# PIR_Relay.net
KiCad netlist of a schematic drawn in EAGLE
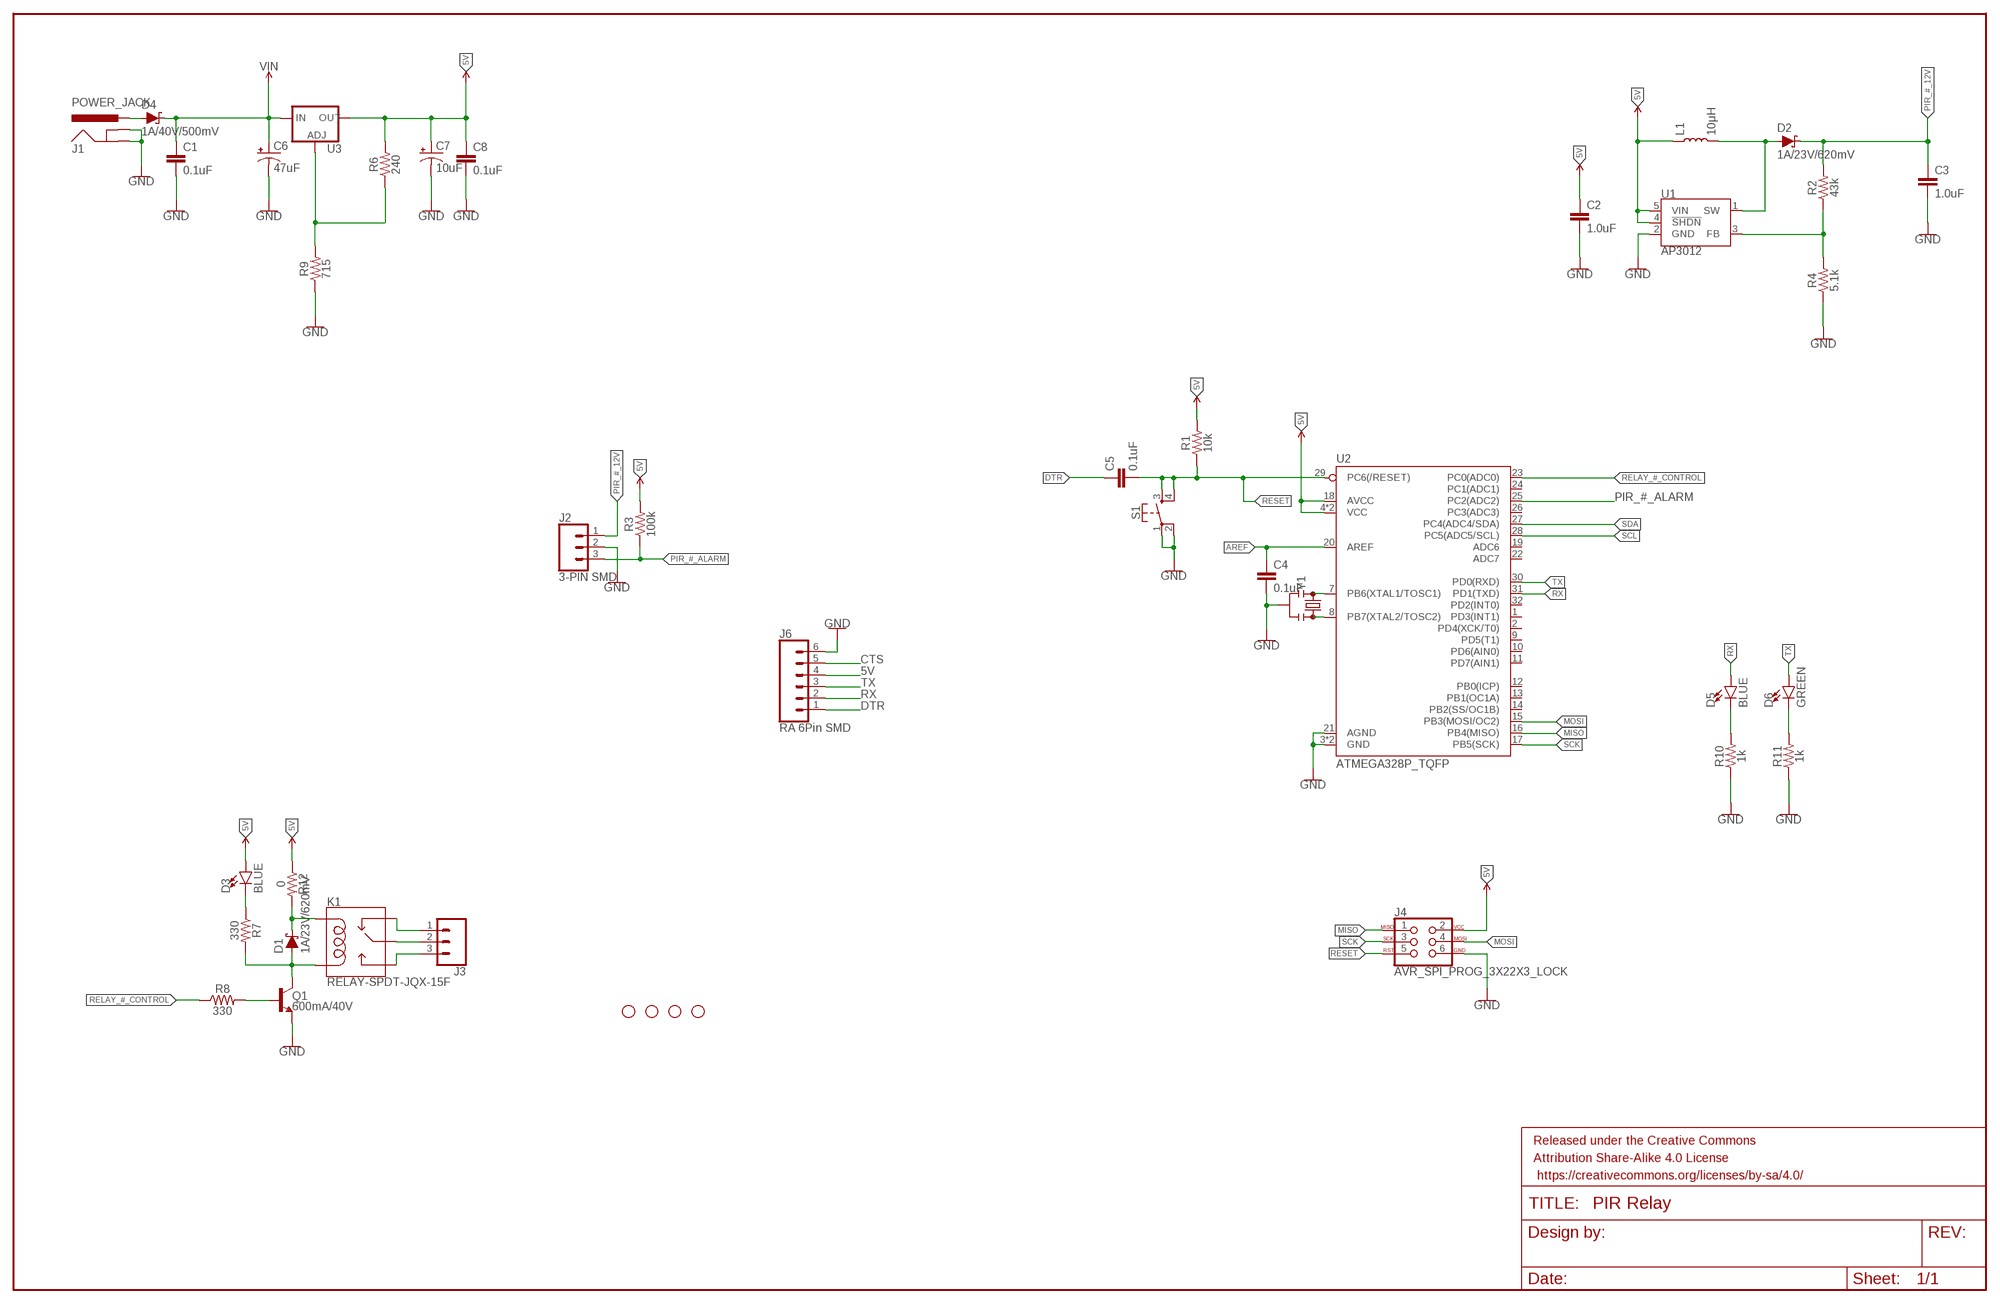
[diagram p0: schematic, sheet 1]

(export (version "E")
  (design (tool "Eeschema 10.0.6"))
  (components
    (comp (ref "C1")
      (value "0.1uF")
      (footprint "eagle-import:0603")
      (libsource (lib "eagle-import") (part "SparkFun-Capacitors_510_0.1UF-0603-25V-5%"))
    )
    (comp (ref "C2")
      (value "1.0uF")
      (footprint "eagle-import:0603")
      (libsource (lib "eagle-import") (part "1.0UF-0603-16V-10%"))
    )
    (comp (ref "C3")
      (value "1.0uF")
      (footprint "eagle-import:0603")
      (libsource (lib "eagle-import") (part "1.0UF-0603-16V-10%"))
    )
    (comp (ref "C4")
      (value "0.1uF")
      (footprint "eagle-import:0603")
      (libsource (lib "eagle-import") (part "0.1UF-0603-25V-(+80/-20%)"))
    )
    (comp (ref "C5")
      (value "0.1uF")
      (footprint "eagle-import:0603")
      (libsource (lib "eagle-import") (part "0.1UF-0603-25V-(+80/-20%)"))
    )
    (comp (ref "C6")
      (value "47uF")
      (footprint "eagle-import:PANASONIC_D")
      (libsource (lib "eagle-import") (part "47UF-POLAR-PANASONIC_D-35V-20%"))
    )
    (comp (ref "C7")
      (value "10uF")
      (footprint "eagle-import:EIA3216")
      (libsource (lib "eagle-import") (part "10UF-POLAR-EIA3216-16V-10%(TANT)"))
    )
    (comp (ref "C8")
      (value "0.1uF")
      (footprint "eagle-import:0603")
      (libsource (lib "eagle-import") (part "0.1UF-0603-25V-(+80/-20%)"))
    )
    (comp (ref "D1")
      (value "1A/23V/620mV")
      (footprint "eagle-import:SOD-323")
      (libsource (lib "eagle-import") (part "DIODE-SCHOTTKY-BAT20J"))
    )
    (comp (ref "D2")
      (value "1A/23V/620mV")
      (footprint "eagle-import:SOD-323")
      (libsource (lib "eagle-import") (part "DIODE-SCHOTTKY-BAT20J"))
    )
    (comp (ref "D3")
      (value "BLUE")
      (footprint "eagle-import:LED-0603")
      (libsource (lib "eagle-import") (part "LED-BLUE0603"))
    )
    (comp (ref "D4")
      (value "1A/40V/500mV")
      (footprint "eagle-import:SMA-DIODE")
      (libsource (lib "eagle-import") (part "DIODE-SCHOTTKY-SS14"))
    )
    (comp (ref "D5")
      (value "BLUE")
      (footprint "eagle-import:LED-0603")
      (libsource (lib "eagle-import") (part "LED-BLUE0603"))
    )
    (comp (ref "D6")
      (value "GREEN")
      (footprint "eagle-import:LED-0603")
      (libsource (lib "eagle-import") (part "LED-GREEN0603"))
    )
    (comp (ref "FRAME1")
      (value "FRAME-LEDGER")
      (footprint "eagle-import:CREATIVE_COMMONS")
      (libsource (lib "eagle-import") (part "FRAME-LEDGER"))
    )
    (comp (ref "H1")
      (value "STAND-OFF")
      (footprint "eagle-import:STAND-OFF")
      (libsource (lib "eagle-import") (part "STAND-OFF"))
    )
    (comp (ref "H2")
      (value "STAND-OFF")
      (footprint "eagle-import:STAND-OFF")
      (libsource (lib "eagle-import") (part "STAND-OFF"))
    )
    (comp (ref "H3")
      (value "STAND-OFF")
      (footprint "eagle-import:STAND-OFF")
      (libsource (lib "eagle-import") (part "STAND-OFF"))
    )
    (comp (ref "H4")
      (value "STAND-OFF")
      (footprint "eagle-import:STAND-OFF")
      (libsource (lib "eagle-import") (part "STAND-OFF"))
    )
    (comp (ref "J1")
      (value "POWER_JACK")
      (footprint "eagle-import:POWER_JACK_PTH")
      (libsource (lib "eagle-import") (part "POWER_JACK"))
    )
    (comp (ref "J2")
      (value "3-PIN SMD")
      (footprint "eagle-import:JST-3-SMD")
      (libsource (lib "eagle-import") (part "CONN_03JST-SMD"))
    )
    (comp (ref "J3")
      (value "CONN_03SCREW_LOCK")
      (footprint "eagle-import:SCREWTERMINAL-3.5MM-3_LOCK.007S")
      (libsource (lib "eagle-import") (part "CONN_03SCREW_LOCK"))
    )
    (comp (ref "J4")
      (value "AVR_SPI_PROG_3X22X3_LOCK")
      (footprint "eagle-import:2X3_LOCK")
      (libsource (lib "eagle-import") (part "AVR_SPI_PROG_3X22X3_LOCK"))
    )
    (comp (ref "J6")
      (value "RA 6Pin SMD")
      (footprint "eagle-import:1X06-SMD_RA_MALE")
      (libsource (lib "eagle-import") (part "CONN_06SMD"))
    )
    (comp (ref "K1")
      (value "RELAY-SPDT-JQX-15F")
      (footprint "eagle-import:RELAY-T90")
      (libsource (lib "eagle-import") (part "RELAY-SPDT-JQX-15F"))
    )
    (comp (ref "L1")
      (value "10μH")
      (footprint "eagle-import:0805")
      (libsource (lib "eagle-import") (part "10μH_SHIELDED_INDUCTOR0805"))
    )
    (comp (ref "Q1")
      (value "600mA/40V")
      (footprint "eagle-import:SOT23-3")
      (libsource (lib "eagle-import") (part "TRANS_NPN-MMBT2222AL"))
    )
    (comp (ref "R1")
      (value "10k")
      (footprint "eagle-import:0603")
      (libsource (lib "eagle-import") (part "10KOHM-0603-1/10W-1%"))
    )
    (comp (ref "R2")
      (value "43k")
      (footprint "eagle-import:0603")
      (libsource (lib "eagle-import") (part "43KOHM-0603-1/10W-1%"))
    )
    (comp (ref "R3")
      (value "100k")
      (footprint "eagle-import:0603")
      (libsource (lib "eagle-import") (part "100KOHM-0603-1/10W-1%"))
    )
    (comp (ref "R4")
      (value "5.1k")
      (footprint "eagle-import:0603")
      (libsource (lib "eagle-import") (part "5.1KOHM5.1KOHM-0603-1/10W-1%"))
    )
    (comp (ref "R6")
      (value "240")
      (footprint "eagle-import:0603")
      (libsource (lib "eagle-import") (part "240OHM-0603-1/10W-1%"))
    )
    (comp (ref "R7")
      (value "330")
      (footprint "eagle-import:0603")
      (libsource (lib "eagle-import") (part "330OHM-0603-1/10W-1%"))
    )
    (comp (ref "R8")
      (value "330")
      (footprint "eagle-import:0603")
      (libsource (lib "eagle-import") (part "330OHM-0603-1/10W-1%"))
    )
    (comp (ref "R9")
      (value "715")
      (footprint "eagle-import:0603")
      (libsource (lib "eagle-import") (part "715OHM-0603-1/10W-1%"))
    )
    (comp (ref "R10")
      (value "1k")
      (footprint "eagle-import:0603")
      (libsource (lib "eagle-import") (part "1KOHM-0603-1/10W-1%"))
    )
    (comp (ref "R11")
      (value "1k")
      (footprint "eagle-import:0603")
      (libsource (lib "eagle-import") (part "1KOHM-0603-1/10W-1%"))
    )
    (comp (ref "R12")
      (value "0")
      (footprint "eagle-import:0603")
      (libsource (lib "eagle-import") (part "0OHM-0603-1/10W"))
    )
    (comp (ref "S1")
      (value "MOMENTARY-SWITCH-SPST-2-SMD-5.2MM-TALL")
      (footprint "eagle-import:TACTILE_SWITCH_SMD_5.2MM")
      (libsource (lib "eagle-import") (part "MOMENTARY-SWITCH-SPST-2-SMD-5.2MM-TALL"))
    )
    (comp (ref "U1")
      (value "AP3012")
      (footprint "eagle-import:SOT23-5")
      (libsource (lib "eagle-import") (part "AP3012"))
    )
    (comp (ref "U2")
      (value "ATMEGA328P_TQFP")
      (footprint "eagle-import:TQFP32-08")
      (libsource (lib "eagle-import") (part "ATMEGA328P_TQFP"))
    )
    (comp (ref "U3")
      (value "V_REG_LM1117SOT223")
      (footprint "eagle-import:SOT223")
      (libsource (lib "eagle-import") (part "V_REG_LM1117SOT223"))
    )
    (comp (ref "Y1")
      (value "RESONATORSMD-3.2X1.3")
      (footprint "eagle-import:RESONATOR-SMD-3.2X1.3")
      (libsource (lib "eagle-import") (part "RESONATORSMD-3.2X1.3"))
    )
  )
  (nets
    (net (code "1") (name "/CTS") (class "Default")
      (node (ref "J6") (pin "5") (pinfunction "5_5") (pintype "passive"))
    )
    (net (code "2") (name "5V") (class "Default")
      (node (ref "C2") (pin "1") (pinfunction "1_1") (pintype "passive"))
      (node (ref "C7") (pin "+") (pinfunction "+_+") (pintype "passive"))
      (node (ref "C8") (pin "1") (pinfunction "1_1") (pintype "passive"))
      (node (ref "D3") (pin "A") (pinfunction "A_A") (pintype "passive"))
      (node (ref "J4") (pin "2") (pinfunction "2_2") (pintype "passive"))
      (node (ref "J6") (pin "4") (pinfunction "4_4") (pintype "passive"))
      (node (ref "L1") (pin "1") (pinfunction "1_1") (pintype "passive"))
      (node (ref "R1") (pin "2") (pinfunction "2_2") (pintype "passive"))
      (node (ref "R12") (pin "1") (pinfunction "1_1") (pintype "passive"))
      (node (ref "R3") (pin "2") (pinfunction "2_2") (pintype "passive"))
      (node (ref "R6") (pin "2") (pinfunction "2_2") (pintype "passive"))
      (node (ref "U1") (pin "4") (pinfunction "~{SHDN}_4") (pintype "bidirectional"))
      (node (ref "U1") (pin "5") (pinfunction "VIN_5") (pintype "bidirectional"))
      (node (ref "U2") (pin "18") (pinfunction "AVCC_18") (pintype "bidirectional"))
      (node (ref "U2") (pin "4") (pinfunction "VCC_4") (pintype "bidirectional"))
      (node (ref "U2") (pin "6") (pinfunction "VCC_6") (pintype "bidirectional"))
      (node (ref "U3") (pin "2") (pinfunction "OUT_2") (pintype "output"))
      (node (ref "U3") (pin "4") (pinfunction "OUT_4") (pintype "output"))
    )
    (net (code "3") (name "AREF") (class "Default")
      (node (ref "C4") (pin "1") (pinfunction "1_1") (pintype "passive"))
      (node (ref "U2") (pin "20") (pinfunction "AREF_20") (pintype "bidirectional"))
    )
    (net (code "4") (name "DTR") (class "Default")
      (node (ref "C5") (pin "1") (pinfunction "1_1") (pintype "passive"))
      (node (ref "J6") (pin "1") (pinfunction "1_1") (pintype "passive"))
    )
    (net (code "5") (name "GND") (class "Default")
      (node (ref "C1") (pin "2") (pinfunction "2_2") (pintype "passive"))
      (node (ref "C2") (pin "2") (pinfunction "2_2") (pintype "passive"))
      (node (ref "C3") (pin "2") (pinfunction "2_2") (pintype "passive"))
      (node (ref "C4") (pin "2") (pinfunction "2_2") (pintype "passive"))
      (node (ref "C6") (pin "-") (pinfunction "-_-") (pintype "passive"))
      (node (ref "C7") (pin "-") (pinfunction "-_-") (pintype "passive"))
      (node (ref "C8") (pin "2") (pinfunction "2_2") (pintype "passive"))
      (node (ref "J1") (pin "GND") (pinfunction "GND_GND") (pintype "bidirectional"))
      (node (ref "J1") (pin "GNDBREAK") (pinfunction "GNDBREAK_GNDBREAK") (pintype "bidirectional"))
      (node (ref "J2") (pin "2") (pinfunction "2_2") (pintype "passive"))
      (node (ref "J4") (pin "6") (pinfunction "6_6") (pintype "passive"))
      (node (ref "J6") (pin "6") (pinfunction "6_6") (pintype "passive"))
      (node (ref "Q1") (pin "2") (pinfunction "E_2") (pintype "passive"))
      (node (ref "R10") (pin "1") (pinfunction "1_1") (pintype "passive"))
      (node (ref "R11") (pin "1") (pinfunction "1_1") (pintype "passive"))
      (node (ref "R4") (pin "1") (pinfunction "1_1") (pintype "passive"))
      (node (ref "R9") (pin "1") (pinfunction "1_1") (pintype "passive"))
      (node (ref "S1") (pin "1") (pinfunction "1_1") (pintype "passive"))
      (node (ref "S1") (pin "2") (pinfunction "2_2") (pintype "passive"))
      (node (ref "U1") (pin "2") (pinfunction "GND_2") (pintype "bidirectional"))
      (node (ref "U2") (pin "21") (pinfunction "AGND_21") (pintype "bidirectional"))
      (node (ref "U2") (pin "3") (pinfunction "GND_3") (pintype "bidirectional"))
      (node (ref "U2") (pin "5") (pinfunction "GND_5") (pintype "bidirectional"))
      (node (ref "Y1") (pin "2") (pinfunction "2_2") (pintype "passive"))
    )
    (net (code "6") (name "MISO") (class "Default")
      (node (ref "J4") (pin "1") (pinfunction "1_1") (pintype "passive"))
      (node (ref "U2") (pin "16") (pinfunction "PB4(MISO)_16") (pintype "bidirectional"))
    )
    (net (code "7") (name "MOSI") (class "Default")
      (node (ref "J4") (pin "4") (pinfunction "4_4") (pintype "passive"))
      (node (ref "U2") (pin "15") (pinfunction "PB3(MOSI/OC2)_15") (pintype "bidirectional"))
    )
    (net (code "8") (name "Net-(D1-PadC)") (class "Default")
      (node (ref "D1") (pin "C") (pinfunction "C_C") (pintype "passive"))
      (node (ref "K1") (pin "COIL1") (pinfunction "COIL1_COIL1") (pintype "bidirectional"))
      (node (ref "R12") (pin "2") (pinfunction "2_2") (pintype "passive"))
    )
    (net (code "9") (name "Net-(D3-PadC)") (class "Default")
      (node (ref "D3") (pin "C") (pinfunction "C_C") (pintype "passive"))
      (node (ref "R7") (pin "1") (pinfunction "1_1") (pintype "passive"))
    )
    (net (code "10") (name "Net-(D4-PadA)") (class "Default")
      (node (ref "D4") (pin "A") (pinfunction "A_A") (pintype "passive"))
      (node (ref "J1") (pin "PWR") (pinfunction "PWR_PWR") (pintype "bidirectional"))
    )
    (net (code "11") (name "Net-(D5-PadC)") (class "Default")
      (node (ref "D5") (pin "C") (pinfunction "C_C") (pintype "passive"))
      (node (ref "R10") (pin "2") (pinfunction "2_2") (pintype "passive"))
    )
    (net (code "12") (name "Net-(D6-PadC)") (class "Default")
      (node (ref "D6") (pin "C") (pinfunction "C_C") (pintype "passive"))
      (node (ref "R11") (pin "2") (pinfunction "2_2") (pintype "passive"))
    )
    (net (code "13") (name "Net-(J3-Pad1)") (class "Default")
      (node (ref "J3") (pin "1") (pinfunction "1_1") (pintype "passive"))
      (node (ref "K1") (pin "NC") (pinfunction "NC_NC") (pintype "bidirectional"))
    )
    (net (code "14") (name "Net-(J3-Pad2)") (class "Default")
      (node (ref "J3") (pin "2") (pinfunction "2_2") (pintype "passive"))
      (node (ref "K1") (pin "MAIN") (pinfunction "MAIN_MAIN") (pintype "bidirectional"))
    )
    (net (code "15") (name "Net-(J3-Pad3)") (class "Default")
      (node (ref "J3") (pin "3") (pinfunction "3_3") (pintype "passive"))
      (node (ref "K1") (pin "NO") (pinfunction "NO_NO") (pintype "bidirectional"))
    )
    (net (code "16") (name "Net-(Q1-B)") (class "Default")
      (node (ref "Q1") (pin "1") (pinfunction "B_1") (pintype "passive"))
      (node (ref "R8") (pin "2") (pinfunction "2_2") (pintype "passive"))
    )
    (net (code "17") (name "Net-(Q1-C)") (class "Default")
      (node (ref "D1") (pin "A") (pinfunction "A_A") (pintype "passive"))
      (node (ref "K1") (pin "COIL2") (pinfunction "COIL2_COIL2") (pintype "bidirectional"))
      (node (ref "Q1") (pin "3") (pinfunction "C_3") (pintype "passive"))
      (node (ref "R7") (pin "2") (pinfunction "2_2") (pintype "passive"))
    )
    (net (code "18") (name "Net-(U1-FB)") (class "Default")
      (node (ref "R2") (pin "1") (pinfunction "1_1") (pintype "passive"))
      (node (ref "R4") (pin "2") (pinfunction "2_2") (pintype "passive"))
      (node (ref "U1") (pin "3") (pinfunction "FB_3") (pintype "bidirectional"))
    )
    (net (code "19") (name "Net-(U1-SW)") (class "Default")
      (node (ref "D2") (pin "A") (pinfunction "A_A") (pintype "passive"))
      (node (ref "L1") (pin "2") (pinfunction "2_2") (pintype "passive"))
      (node (ref "U1") (pin "1") (pinfunction "SW_1") (pintype "bidirectional"))
    )
    (net (code "20") (name "Net-(U2-PB6(XTAL1{slash}TOSC1))") (class "Default")
      (node (ref "U2") (pin "7") (pinfunction "PB6(XTAL1/TOSC1)_7") (pintype "bidirectional"))
      (node (ref "Y1") (pin "1") (pinfunction "1_1") (pintype "passive"))
    )
    (net (code "21") (name "Net-(U2-PB7(XTAL2{slash}TOSC2))") (class "Default")
      (node (ref "U2") (pin "8") (pinfunction "PB7(XTAL2/TOSC2)_8") (pintype "bidirectional"))
      (node (ref "Y1") (pin "3") (pinfunction "3_3") (pintype "passive"))
    )
    (net (code "22") (name "Net-(U3-ADJ)") (class "Default")
      (node (ref "R6") (pin "1") (pinfunction "1_1") (pintype "passive"))
      (node (ref "R9") (pin "2") (pinfunction "2_2") (pintype "passive"))
      (node (ref "U3") (pin "1") (pinfunction "ADJ_1") (pintype "input"))
    )
    (net (code "23") (name "PIR_#_12V") (class "Default")
      (node (ref "C3") (pin "1") (pinfunction "1_1") (pintype "passive"))
      (node (ref "D2") (pin "C") (pinfunction "C_C") (pintype "passive"))
      (node (ref "J2") (pin "1") (pinfunction "3_1") (pintype "passive"))
      (node (ref "R2") (pin "2") (pinfunction "2_2") (pintype "passive"))
    )
    (net (code "24") (name "PIR_#_ALARM") (class "Default")
      (node (ref "J2") (pin "3") (pinfunction "1_3") (pintype "passive"))
      (node (ref "R3") (pin "1") (pinfunction "1_1") (pintype "passive"))
      (node (ref "U2") (pin "25") (pinfunction "PC2(ADC2)_25") (pintype "bidirectional"))
    )
    (net (code "25") (name "RELAY_#_CONTROL") (class "Default")
      (node (ref "R8") (pin "1") (pinfunction "1_1") (pintype "passive"))
      (node (ref "U2") (pin "23") (pinfunction "PC0(ADC0)_23") (pintype "bidirectional"))
    )
    (net (code "26") (name "RESET") (class "Default")
      (node (ref "C5") (pin "2") (pinfunction "2_2") (pintype "passive"))
      (node (ref "J4") (pin "5") (pinfunction "5_5") (pintype "passive"))
      (node (ref "R1") (pin "1") (pinfunction "1_1") (pintype "passive"))
      (node (ref "S1") (pin "3") (pinfunction "3_3") (pintype "passive"))
      (node (ref "S1") (pin "4") (pinfunction "4_4") (pintype "passive"))
      (node (ref "U2") (pin "29") (pinfunction "PC6(/RESET)_29") (pintype "bidirectional"))
    )
    (net (code "27") (name "RX") (class "Default")
      (node (ref "D5") (pin "A") (pinfunction "A_A") (pintype "passive"))
      (node (ref "J6") (pin "2") (pinfunction "2_2") (pintype "passive"))
      (node (ref "U2") (pin "31") (pinfunction "PD1(TXD)_31") (pintype "bidirectional"))
    )
    (net (code "28") (name "SCK") (class "Default")
      (node (ref "J4") (pin "3") (pinfunction "3_3") (pintype "passive"))
      (node (ref "U2") (pin "17") (pinfunction "PB5(SCK)_17") (pintype "bidirectional"))
    )
    (net (code "29") (name "SCL") (class "Default")
      (node (ref "U2") (pin "28") (pinfunction "PC5(ADC5/SCL)_28") (pintype "bidirectional"))
    )
    (net (code "30") (name "SDA") (class "Default")
      (node (ref "U2") (pin "27") (pinfunction "PC4(ADC4/SDA)_27") (pintype "bidirectional"))
    )
    (net (code "31") (name "TX") (class "Default")
      (node (ref "D6") (pin "A") (pinfunction "A_A") (pintype "passive"))
      (node (ref "J6") (pin "3") (pinfunction "3_3") (pintype "passive"))
      (node (ref "U2") (pin "30") (pinfunction "PD0(RXD)_30") (pintype "bidirectional"))
    )
    (net (code "32") (name "VIN") (class "Default")
      (node (ref "C1") (pin "1") (pinfunction "1_1") (pintype "passive"))
      (node (ref "C6") (pin "+") (pinfunction "+_+") (pintype "passive"))
      (node (ref "D4") (pin "C") (pinfunction "C_C") (pintype "passive"))
      (node (ref "U3") (pin "3") (pinfunction "IN_3") (pintype "input"))
    )
    (net (code "33") (name "unconnected-(U2-ADC6-Pad19)") (class "Default")
      (node (ref "U2") (pin "19") (pinfunction "ADC6_19") (pintype "bidirectional"))
    )
    (net (code "34") (name "unconnected-(U2-ADC7-Pad22)") (class "Default")
      (node (ref "U2") (pin "22") (pinfunction "ADC7_22") (pintype "bidirectional"))
    )
    (net (code "35") (name "unconnected-(U2-PB0(ICP)-Pad12)") (class "Default")
      (node (ref "U2") (pin "12") (pinfunction "PB0(ICP)_12") (pintype "bidirectional"))
    )
    (net (code "36") (name "unconnected-(U2-PB1(OC1A)-Pad13)") (class "Default")
      (node (ref "U2") (pin "13") (pinfunction "PB1(OC1A)_13") (pintype "bidirectional"))
    )
    (net (code "37") (name "unconnected-(U2-PB2(SS{slash}OC1B)-Pad14)") (class "Default")
      (node (ref "U2") (pin "14") (pinfunction "PB2(SS/OC1B)_14") (pintype "bidirectional"))
    )
    (net (code "38") (name "unconnected-(U2-PC1(ADC1)-Pad24)") (class "Default")
      (node (ref "U2") (pin "24") (pinfunction "PC1(ADC1)_24") (pintype "bidirectional"))
    )
    (net (code "39") (name "unconnected-(U2-PC3(ADC3)-Pad26)") (class "Default")
      (node (ref "U2") (pin "26") (pinfunction "PC3(ADC3)_26") (pintype "bidirectional"))
    )
    (net (code "40") (name "unconnected-(U2-PD2(INT0)-Pad32)") (class "Default")
      (node (ref "U2") (pin "32") (pinfunction "PD2(INT0)_32") (pintype "bidirectional"))
    )
    (net (code "41") (name "unconnected-(U2-PD3(INT1)-Pad1)") (class "Default")
      (node (ref "U2") (pin "1") (pinfunction "PD3(INT1)_1") (pintype "bidirectional"))
    )
    (net (code "42") (name "unconnected-(U2-PD4(XCK{slash}T0)-Pad2)") (class "Default")
      (node (ref "U2") (pin "2") (pinfunction "PD4(XCK/T0)_2") (pintype "bidirectional"))
    )
    (net (code "43") (name "unconnected-(U2-PD5(T1)-Pad9)") (class "Default")
      (node (ref "U2") (pin "9") (pinfunction "PD5(T1)_9") (pintype "bidirectional"))
    )
    (net (code "44") (name "unconnected-(U2-PD6(AIN0)-Pad10)") (class "Default")
      (node (ref "U2") (pin "10") (pinfunction "PD6(AIN0)_10") (pintype "bidirectional"))
    )
    (net (code "45") (name "unconnected-(U2-PD7(AIN1)-Pad11)") (class "Default")
      (node (ref "U2") (pin "11") (pinfunction "PD7(AIN1)_11") (pintype "bidirectional"))
    )
  )
)
